# programmer.net
KiCad netlist of a schematic drawn in EAGLE
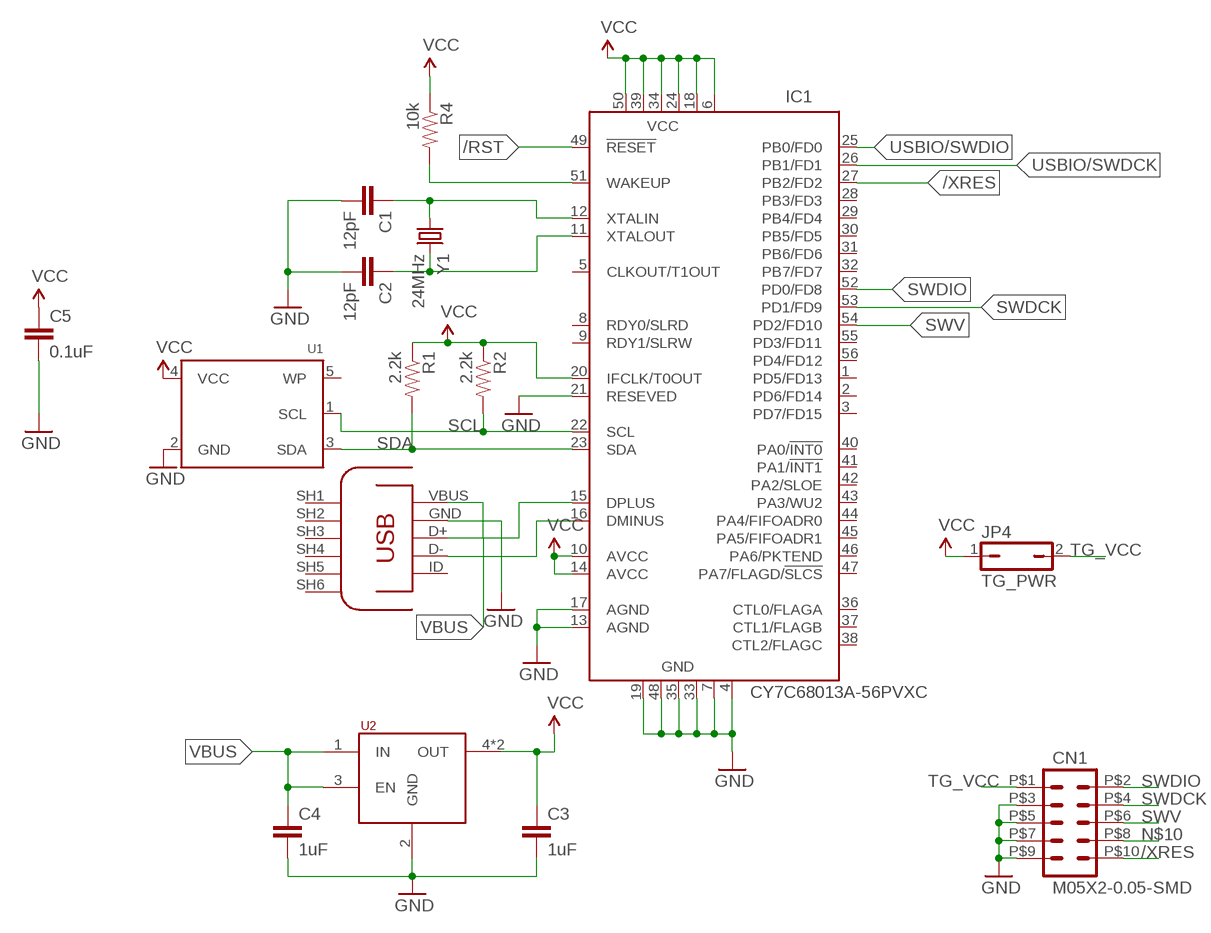
[diagram p0: schematic, sheet 1]

(export (version "E")
  (design (tool "Eeschema 10.0.6"))
  (components
    (comp (ref "C1")
      (value "12pF")
      (footprint "eagle-import:0805")
      (libsource (lib "eagle-import") (part "CAP0805"))
    )
    (comp (ref "C2")
      (value "12pF")
      (footprint "eagle-import:0805")
      (libsource (lib "eagle-import") (part "CAP0805"))
    )
    (comp (ref "C3")
      (value "1uF")
      (footprint "eagle-import:0805")
      (libsource (lib "eagle-import") (part "CAP0805"))
    )
    (comp (ref "C4")
      (value "1uF")
      (footprint "eagle-import:0805")
      (libsource (lib "eagle-import") (part "CAP0805"))
    )
    (comp (ref "C5")
      (value "0.1uF")
      (footprint "eagle-import:0805")
      (libsource (lib "eagle-import") (part "CAP0805"))
    )
    (comp (ref "CN1")
      (value "M05X2-0.05-SMD")
      (footprint "eagle-import:PINHD-2X5-0.05-SMD")
      (libsource (lib "eagle-import") (part "M05X2-0.05-SMD"))
    )
    (comp (ref "IC1")
      (value "CY7C68013A-56PVXC")
      (footprint "eagle-import:SSOP56")
      (fields (field (name "MF") "CYPRESS SEMICONDUCTOR CORPORAT"))
      (libsource (lib "eagle-import") (part "CY7C6801A-56PVXC3"))
    )
    (comp (ref "JP4")
      (value "TG_PWR")
      (footprint "eagle-import:JP1")
      (libsource (lib "eagle-import") (part "JP1Q"))
    )
    (comp (ref "R1")
      (value "2.2k")
      (footprint "eagle-import:0805")
      (libsource (lib "eagle-import") (part "RESISTOR0805-RES"))
    )
    (comp (ref "R2")
      (value "2.2k")
      (footprint "eagle-import:0805")
      (libsource (lib "eagle-import") (part "RESISTOR0805-RES"))
    )
    (comp (ref "R4")
      (value "10k")
      (footprint "eagle-import:0805")
      (libsource (lib "eagle-import") (part "RESISTOR0805-RES"))
    )
    (comp (ref "U$3")
      (value "MICROUSB")
      (footprint "eagle-import:USB-MICROB")
      (libsource (lib "eagle-import") (part "MICROUSB"))
    )
    (comp (ref "U1")
      (value "EEPROM_I2C_MCP24AA32")
      (footprint "eagle-import:SOT23-5")
      (libsource (lib "eagle-import") (part "EEPROM_I2C_MCP24AA32"))
    )
    (comp (ref "U2")
      (value "TLV702XX")
      (footprint "eagle-import:SOT23-5")
      (libsource (lib "eagle-import") (part "TLV702XX"))
    )
    (comp (ref "Y1")
      (value "24MHz")
      (footprint "eagle-import:XRCGB-XTAL")
      (libsource (lib "eagle-import") (part "XRCGB_XTAL"))
    )
  )
  (nets
    (net (code "1") (name "/N$10") (class "Default")
      (node (ref "CN1") (pin "P$8") (pinfunction "8_P$8") (pintype "passive"))
    )
    (net (code "2") (name "/SCL") (class "Default")
      (node (ref "IC1") (pin "22") (pinfunction "SCL_22") (pintype "output"))
      (node (ref "R2") (pin "2") (pinfunction "2_2") (pintype "passive"))
      (node (ref "U1") (pin "1") (pinfunction "SCL_1") (pintype "bidirectional"))
    )
    (net (code "3") (name "/SDA") (class "Default")
      (node (ref "IC1") (pin "23") (pinfunction "SDA_23") (pintype "bidirectional"))
      (node (ref "R1") (pin "2") (pinfunction "2_2") (pintype "passive"))
      (node (ref "U1") (pin "3") (pinfunction "SDA_3") (pintype "bidirectional"))
    )
    (net (code "4") (name "/TG_VCC") (class "Default")
      (node (ref "CN1") (pin "P$1") (pinfunction "1_P$1") (pintype "passive"))
      (node (ref "JP4") (pin "2") (pinfunction "2_2") (pintype "passive"))
    )
    (net (code "5") (name "GND") (class "Default")
      (node (ref "C1") (pin "2") (pinfunction "2_2") (pintype "passive"))
      (node (ref "C2") (pin "2") (pinfunction "2_2") (pintype "passive"))
      (node (ref "C3") (pin "2") (pinfunction "2_2") (pintype "passive"))
      (node (ref "C4") (pin "2") (pinfunction "2_2") (pintype "passive"))
      (node (ref "C5") (pin "2") (pinfunction "2_2") (pintype "passive"))
      (node (ref "CN1") (pin "P$3") (pinfunction "3_P$3") (pintype "passive"))
      (node (ref "CN1") (pin "P$5") (pinfunction "5_P$5") (pintype "passive"))
      (node (ref "CN1") (pin "P$7") (pinfunction "7_P$7") (pintype "passive"))
      (node (ref "CN1") (pin "P$9") (pinfunction "9_P$9") (pintype "passive"))
      (node (ref "IC1") (pin "13") (pinfunction "AGND_13") (pintype "input"))
      (node (ref "IC1") (pin "17") (pinfunction "AGND_17") (pintype "input"))
      (node (ref "IC1") (pin "19") (pinfunction "GND_19") (pintype "input"))
      (node (ref "IC1") (pin "21") (pinfunction "RESEVED_21") (pintype "input"))
      (node (ref "IC1") (pin "33") (pinfunction "GND_33") (pintype "input"))
      (node (ref "IC1") (pin "35") (pinfunction "GND_35") (pintype "input"))
      (node (ref "IC1") (pin "4") (pinfunction "GND_4") (pintype "input"))
      (node (ref "IC1") (pin "48") (pinfunction "GND_48") (pintype "input"))
      (node (ref "IC1") (pin "7") (pinfunction "GND_7") (pintype "input"))
      (node (ref "U$3") (pin "GND") (pinfunction "GND_GND") (pintype "bidirectional"))
      (node (ref "U1") (pin "2") (pinfunction "GND_2") (pintype "bidirectional"))
      (node (ref "U2") (pin "2") (pinfunction "GND_2") (pintype "power_in"))
    )
    (net (code "6") (name "Net-(IC1-DMINUS)") (class "Default")
      (node (ref "IC1") (pin "16") (pinfunction "DMINUS_16") (pintype "bidirectional"))
      (node (ref "U$3") (pin "D-") (pinfunction "D-_D-") (pintype "bidirectional"))
    )
    (net (code "7") (name "Net-(IC1-DPLUS)") (class "Default")
      (node (ref "IC1") (pin "15") (pinfunction "DPLUS_15") (pintype "bidirectional"))
      (node (ref "U$3") (pin "D+") (pinfunction "D+_D+") (pintype "bidirectional"))
    )
    (net (code "8") (name "Net-(IC1-WAKEUP)") (class "Default")
      (node (ref "IC1") (pin "51") (pinfunction "WAKEUP_51") (pintype "input"))
      (node (ref "R4") (pin "2") (pinfunction "2_2") (pintype "passive"))
    )
    (net (code "9") (name "Net-(IC1-XTALIN)") (class "Default")
      (node (ref "C1") (pin "1") (pinfunction "1_1") (pintype "passive"))
      (node (ref "IC1") (pin "12") (pinfunction "XTALIN_12") (pintype "input"))
      (node (ref "Y1") (pin "1") (pinfunction "1_1") (pintype "passive"))
    )
    (net (code "10") (name "Net-(IC1-XTALOUT)") (class "Default")
      (node (ref "C2") (pin "1") (pinfunction "1_1") (pintype "passive"))
      (node (ref "IC1") (pin "11") (pinfunction "XTALOUT_11") (pintype "input"))
      (node (ref "Y1") (pin "2") (pinfunction "2_2") (pintype "passive"))
    )
    (net (code "11") (name "SWDCK") (class "Default")
      (node (ref "CN1") (pin "P$4") (pinfunction "4_P$4") (pintype "passive"))
      (node (ref "IC1") (pin "53") (pinfunction "PD1/FD9_53") (pintype "bidirectional"))
    )
    (net (code "12") (name "SWDIO") (class "Default")
      (node (ref "CN1") (pin "P$2") (pinfunction "2_P$2") (pintype "passive"))
      (node (ref "IC1") (pin "52") (pinfunction "PD0/FD8_52") (pintype "bidirectional"))
    )
    (net (code "13") (name "SWV") (class "Default")
      (node (ref "CN1") (pin "P$6") (pinfunction "6_P$6") (pintype "passive"))
      (node (ref "IC1") (pin "54") (pinfunction "PD2/FD10_54") (pintype "bidirectional"))
    )
    (net (code "14") (name "USBIO{slash}SWDCK") (class "Default")
      (node (ref "IC1") (pin "26") (pinfunction "PB1/FD1_26") (pintype "bidirectional"))
    )
    (net (code "15") (name "USBIO{slash}SWDIO") (class "Default")
      (node (ref "IC1") (pin "25") (pinfunction "PB0/FD0_25") (pintype "bidirectional"))
    )
    (net (code "16") (name "VBUS") (class "Default")
      (node (ref "C4") (pin "1") (pinfunction "1_1") (pintype "passive"))
      (node (ref "U$3") (pin "VBUS") (pinfunction "VCC_VBUS") (pintype "bidirectional"))
      (node (ref "U2") (pin "1") (pinfunction "IN_1") (pintype "power_in"))
      (node (ref "U2") (pin "3") (pinfunction "EN_3") (pintype "input"))
    )
    (net (code "17") (name "VCC") (class "Default")
      (node (ref "C3") (pin "1") (pinfunction "1_1") (pintype "passive"))
      (node (ref "C5") (pin "1") (pinfunction "1_1") (pintype "passive"))
      (node (ref "IC1") (pin "10") (pinfunction "AVCC_10") (pintype "input"))
      (node (ref "IC1") (pin "14") (pinfunction "AVCC_14") (pintype "input"))
      (node (ref "IC1") (pin "18") (pinfunction "VCC_18") (pintype "input"))
      (node (ref "IC1") (pin "20") (pinfunction "IFCLK/T0OUT_20") (pintype "bidirectional"))
      (node (ref "IC1") (pin "24") (pinfunction "VCC_24") (pintype "input"))
      (node (ref "IC1") (pin "34") (pinfunction "VCC_34") (pintype "input"))
      (node (ref "IC1") (pin "39") (pinfunction "VCC_39") (pintype "input"))
      (node (ref "IC1") (pin "50") (pinfunction "VCC_50") (pintype "input"))
      (node (ref "IC1") (pin "6") (pinfunction "VCC_6") (pintype "input"))
      (node (ref "JP4") (pin "1") (pinfunction "1_1") (pintype "passive"))
      (node (ref "R1") (pin "1") (pinfunction "1_1") (pintype "passive"))
      (node (ref "R2") (pin "1") (pinfunction "1_1") (pintype "passive"))
      (node (ref "R4") (pin "1") (pinfunction "1_1") (pintype "passive"))
      (node (ref "U1") (pin "4") (pinfunction "VCC_4") (pintype "bidirectional"))
      (node (ref "U2") (pin "4") (pinfunction "OUT_4") (pintype "power_in"))
      (node (ref "U2") (pin "5") (pinfunction "OUT_5") (pintype "power_in"))
    )
    (net (code "18") (name "unconnected-(IC1-CLKOUT{slash}T1OUT-Pad5)") (class "Default")
      (node (ref "IC1") (pin "5") (pinfunction "CLKOUT/T1OUT_5") (pintype "input"))
    )
    (net (code "19") (name "unconnected-(IC1-CTL0{slash}FLAGA-Pad36)") (class "Default")
      (node (ref "IC1") (pin "36") (pinfunction "CTL0/FLAGA_36") (pintype "output"))
    )
    (net (code "20") (name "unconnected-(IC1-CTL1{slash}FLAGB-Pad37)") (class "Default")
      (node (ref "IC1") (pin "37") (pinfunction "CTL1/FLAGB_37") (pintype "output"))
    )
    (net (code "21") (name "unconnected-(IC1-CTL2{slash}FLAGC-Pad38)") (class "Default")
      (node (ref "IC1") (pin "38") (pinfunction "CTL2/FLAGC_38") (pintype "output"))
    )
    (net (code "22") (name "unconnected-(IC1-PA0{slash}~{INT0}-Pad40)") (class "Default")
      (node (ref "IC1") (pin "40") (pinfunction "PA0/~{INT0}_40") (pintype "bidirectional"))
    )
    (net (code "23") (name "unconnected-(IC1-PA1{slash}~{INT1}-Pad41)") (class "Default")
      (node (ref "IC1") (pin "41") (pinfunction "PA1/~{INT1}_41") (pintype "bidirectional"))
    )
    (net (code "24") (name "unconnected-(IC1-PA2{slash}SLOE-Pad42)") (class "Default")
      (node (ref "IC1") (pin "42") (pinfunction "PA2/SLOE_42") (pintype "bidirectional"))
    )
    (net (code "25") (name "unconnected-(IC1-PA3{slash}WU2-Pad43)") (class "Default")
      (node (ref "IC1") (pin "43") (pinfunction "PA3/WU2_43") (pintype "bidirectional"))
    )
    (net (code "26") (name "unconnected-(IC1-PA4{slash}FIFOADR0-Pad44)") (class "Default")
      (node (ref "IC1") (pin "44") (pinfunction "PA4/FIFOADR0_44") (pintype "bidirectional"))
    )
    (net (code "27") (name "unconnected-(IC1-PA5{slash}FIFOADR1-Pad45)") (class "Default")
      (node (ref "IC1") (pin "45") (pinfunction "PA5/FIFOADR1_45") (pintype "bidirectional"))
    )
    (net (code "28") (name "unconnected-(IC1-PA6{slash}PKTEND-Pad46)") (class "Default")
      (node (ref "IC1") (pin "46") (pinfunction "PA6/PKTEND_46") (pintype "bidirectional"))
    )
    (net (code "29") (name "unconnected-(IC1-PA7{slash}FLAGD{slash}~{SLCS}-Pad47)") (class "Default")
      (node (ref "IC1") (pin "47") (pinfunction "PA7/FLAGD/~{SLCS}_47") (pintype "bidirectional"))
    )
    (net (code "30") (name "unconnected-(IC1-PB3{slash}FD3-Pad28)") (class "Default")
      (node (ref "IC1") (pin "28") (pinfunction "PB3/FD3_28") (pintype "bidirectional"))
    )
    (net (code "31") (name "unconnected-(IC1-PB4{slash}FD4-Pad29)") (class "Default")
      (node (ref "IC1") (pin "29") (pinfunction "PB4/FD4_29") (pintype "bidirectional"))
    )
    (net (code "32") (name "unconnected-(IC1-PB5{slash}FD5-Pad30)") (class "Default")
      (node (ref "IC1") (pin "30") (pinfunction "PB5/FD5_30") (pintype "bidirectional"))
    )
    (net (code "33") (name "unconnected-(IC1-PB6{slash}FD6-Pad31)") (class "Default")
      (node (ref "IC1") (pin "31") (pinfunction "PB6/FD6_31") (pintype "bidirectional"))
    )
    (net (code "34") (name "unconnected-(IC1-PB7{slash}FD7-Pad32)") (class "Default")
      (node (ref "IC1") (pin "32") (pinfunction "PB7/FD7_32") (pintype "bidirectional"))
    )
    (net (code "35") (name "unconnected-(IC1-PD3{slash}FD11-Pad55)") (class "Default")
      (node (ref "IC1") (pin "55") (pinfunction "PD3/FD11_55") (pintype "bidirectional"))
    )
    (net (code "36") (name "unconnected-(IC1-PD4{slash}FD12-Pad56)") (class "Default")
      (node (ref "IC1") (pin "56") (pinfunction "PD4/FD12_56") (pintype "bidirectional"))
    )
    (net (code "37") (name "unconnected-(IC1-PD5{slash}FD13-Pad1)") (class "Default")
      (node (ref "IC1") (pin "1") (pinfunction "PD5/FD13_1") (pintype "bidirectional"))
    )
    (net (code "38") (name "unconnected-(IC1-PD6{slash}FD14-Pad2)") (class "Default")
      (node (ref "IC1") (pin "2") (pinfunction "PD6/FD14_2") (pintype "bidirectional"))
    )
    (net (code "39") (name "unconnected-(IC1-PD7{slash}FD15-Pad3)") (class "Default")
      (node (ref "IC1") (pin "3") (pinfunction "PD7/FD15_3") (pintype "bidirectional"))
    )
    (net (code "40") (name "unconnected-(IC1-RDY0{slash}SLRD-Pad8)") (class "Default")
      (node (ref "IC1") (pin "8") (pinfunction "RDY0/SLRD_8") (pintype "input"))
    )
    (net (code "41") (name "unconnected-(IC1-RDY1{slash}SLRW-Pad9)") (class "Default")
      (node (ref "IC1") (pin "9") (pinfunction "RDY1/SLRW_9") (pintype "input"))
    )
    (net (code "42") (name "unconnected-(U$3-PadID)") (class "Default")
      (node (ref "U$3") (pin "ID") (pinfunction "ID_ID") (pintype "bidirectional"))
    )
    (net (code "43") (name "unconnected-(U$3-SH-PadSH1)") (class "Default")
      (node (ref "U$3") (pin "SH1") (pinfunction "SH_SH1") (pintype "bidirectional"))
    )
    (net (code "44") (name "unconnected-(U$3-SH-PadSH2)") (class "Default")
      (node (ref "U$3") (pin "SH2") (pinfunction "SH_SH2") (pintype "bidirectional"))
    )
    (net (code "45") (name "unconnected-(U$3-SH-PadSH3)") (class "Default")
      (node (ref "U$3") (pin "SH3") (pinfunction "SH_SH3") (pintype "bidirectional"))
    )
    (net (code "46") (name "unconnected-(U$3-SH-PadSH4)") (class "Default")
      (node (ref "U$3") (pin "SH4") (pinfunction "SH_SH4") (pintype "bidirectional"))
    )
    (net (code "47") (name "unconnected-(U$3-SH-PadSH5)") (class "Default")
      (node (ref "U$3") (pin "SH5") (pinfunction "SH_SH5") (pintype "bidirectional"))
    )
    (net (code "48") (name "unconnected-(U$3-SH-PadSH6)") (class "Default")
      (node (ref "U$3") (pin "SH6") (pinfunction "SH_SH6") (pintype "bidirectional"))
    )
    (net (code "49") (name "unconnected-(U1-WP-Pad5)") (class "Default")
      (node (ref "U1") (pin "5") (pinfunction "WP_5") (pintype "bidirectional"))
    )
    (net (code "50") (name "{slash}RST") (class "Default")
      (node (ref "IC1") (pin "49") (pinfunction "~{RESET}_49") (pintype "input"))
    )
    (net (code "51") (name "{slash}XRES") (class "Default")
      (node (ref "CN1") (pin "P$10") (pinfunction "10_P$10") (pintype "passive"))
      (node (ref "IC1") (pin "27") (pinfunction "PB2/FD2_27") (pintype "bidirectional"))
    )
  )
)
